# Power.net
KiCad netlist of a schematic drawn in Altium Designer
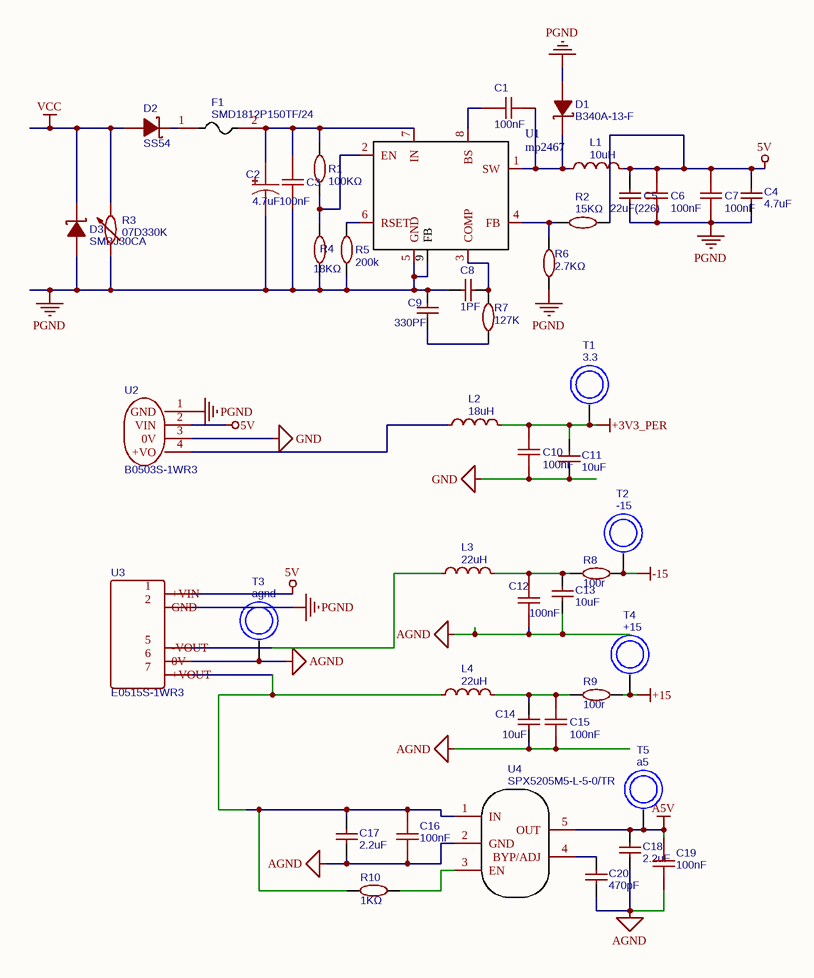
[diagram p0: Power.SchDoc]

(export (version "E")
  (design (tool "Eeschema 10.0.6"))
  (components
    (comp (ref "C1")
      (value "100nF")
      (footprint "0603 - cap")
      (fields (field (name "BOM_MANUFACTURER PART") "CC0603KRX7R9BB104"))
      (libsource (lib "") (part "root_2___1"))
    )
    (comp (ref "C2")
      (value "4.7uF")
      (footprint "CAP-6.3*5.4")
      (fields (field (name "BOM_MANUFACTURER PART") "RVT2A4R7M0605"))
      (libsource (lib "") (part "root_0___8"))
    )
    (comp (ref "C3")
      (value "100nF")
      (footprint "0603 - cap")
      (fields (field (name "BOM_MANUFACTURER PART") "CC0603KRX7R9BB104"))
      (libsource (lib "") (part "root_1___1"))
    )
    (comp (ref "C4")
      (value "4.7uF")
      (footprint "1206 - cap")
      (fields (field (name "BOM_MANUFACTURER PART") "1206B475K500NT"))
      (libsource (lib "") (part "root_1___3"))
    )
    (comp (ref "C5")
      (value "22uF(226)")
      (footprint "1206 - cap")
      (fields (field (name "BOM_MANUFACTURER PART") "1206F226M100NT") (field (name "CONTRIBUTOR") "LCSC"))
      (libsource (lib "altium-import") (part "root_1__"))
    )
    (comp (ref "C6")
      (value "100nF")
      (footprint "0603 - cap")
      (fields (field (name "BOM_MANUFACTURER PART") "CC0603KRX7R9BB104"))
      (libsource (lib "") (part "root_1___1"))
    )
    (comp (ref "C7")
      (value "100nF")
      (footprint "0603 - cap")
      (fields (field (name "BOM_MANUFACTURER PART") "CC0603KRX7R9BB104"))
      (libsource (lib "") (part "root_1___1"))
    )
    (comp (ref "C8")
      (value "1PF")
      (footprint "0603 - cap")
      (fields (field (name "BOM_MANUFACTURER PART") "0603B472K500NT"))
      (libsource (lib "altium-import") (part "root_2__"))
    )
    (comp (ref "C9")
      (value "330PF")
      (footprint "0603 - cap")
      (fields (field (name "BOM_MANUFACTURER PART") "0603B472K500NT"))
      (libsource (lib "") (part "root_1___3"))
    )
    (comp (ref "C10")
      (value "100nF")
      (footprint "0603 - cap")
      (fields (field (name "BOM_MANUFACTURER PART") "CC0603KRX7R9BB104"))
      (libsource (lib "") (part "root_1___1"))
    )
    (comp (ref "C11")
      (value "10uF")
      (footprint "1206 - cap")
      (fields (field (name "BOM_MANUFACTURER PART") "CL31B225KBHNNNE"))
      (libsource (lib "altium-import") (part "root_3__"))
    )
    (comp (ref "C12")
      (value "100nF")
      (footprint "0603 - cap")
      (fields (field (name "BOM_MANUFACTURER PART") "CC0603KRX7R9BB104"))
      (libsource (lib "") (part "root_1___1"))
    )
    (comp (ref "C13")
      (value "10uF")
      (footprint "1206 - cap")
      (fields (field (name "BOM_MANUFACTURER PART") "CL31B225KBHNNNE"))
      (libsource (lib "altium-import") (part "root_3__"))
    )
    (comp (ref "C14")
      (value "10uF")
      (footprint "1206 - cap")
      (fields (field (name "BOM_MANUFACTURER PART") "CL31B225KBHNNNE"))
      (libsource (lib "altium-import") (part "root_3__"))
    )
    (comp (ref "C15")
      (value "100nF")
      (footprint "0603 - cap")
      (fields (field (name "BOM_MANUFACTURER PART") "CC0603KRX7R9BB104"))
      (libsource (lib "") (part "root_1___1"))
    )
    (comp (ref "C16")
      (value "100nF")
      (footprint "0603 - cap")
      (fields (field (name "BOM_MANUFACTURER PART") "CC0603KRX7R9BB104"))
      (libsource (lib "") (part "root_3___1"))
    )
    (comp (ref "C17")
      (value "2.2uF")
      (footprint "1206 - cap")
      (fields (field (name "BOM_MANUFACTURER PART") "CL31B225KBHNNNE"))
      (libsource (lib "altium-import") (part "root_3__"))
    )
    (comp (ref "C18")
      (value "2.2uF")
      (footprint "1206 - cap")
      (fields (field (name "BOM_MANUFACTURER PART") "CL31B225KBHNNNE"))
      (libsource (lib "") (part "root_1___4"))
    )
    (comp (ref "C19")
      (value "100nF")
      (footprint "0603 - cap")
      (fields (field (name "BOM_MANUFACTURER PART") "CC0603KRX7R9BB104"))
      (libsource (lib "") (part "root_1___1"))
    )
    (comp (ref "C20")
      (value "470pF")
      (footprint "0603 - cap")
      (fields (field (name "BOM_MANUFACTURER PART") "0603B471K500NT"))
      (libsource (lib "") (part "root_1___3"))
    )
    (comp (ref "D1")
      (value "B340A-13-F")
      (footprint "SMA(DO-214AC)")
      (libsource (lib "") (part "root_1___5"))
    )
    (comp (ref "D2") (value "SS54") (footprint "SMA(DO-214AC)") (libsource (lib "") (part "root_0___4")))
    (comp (ref "D3") (value "SMBJ30CA") (footprint "SMB(DO-214AA)") (libsource (lib "") (part "root_0___6")))
    (comp (ref "F1") (value "SMD1812P150TF/24") (footprint "1812") (libsource (lib "") (part "root_0___5")))
    (comp (ref "L1")
      (value "10uH")
      (footprint "8040")
      (fields (field (name "BOM_MANUFACTURER PART") "VLP8040T-100M"))
      (libsource (lib "altium-import") (part "root_0__"))
    )
    (comp (ref "L2")
      (value "18uH")
      (footprint "1220")
      (fields (field (name "BOM_MANUFACTURER PART") "SPH252012H180MT"))
      (libsource (lib "") (part "root_0___3"))
    )
    (comp (ref "L3")
      (value "22uH")
      (footprint "IND_0805")
      (fields (field (name "BOM_MANUFACTURER PART") "VLP8040T-100M"))
      (libsource (lib "altium-import") (part "root_0__"))
    )
    (comp (ref "L4")
      (value "22uH")
      (footprint "IND_0805")
      (fields (field (name "BOM_MANUFACTURER PART") "VLP8040T-100M"))
      (libsource (lib "altium-import") (part "root_0__"))
    )
    (comp (ref "R1")
      (value "100KΩ")
      (footprint "0603-res")
      (fields (field (name "BOM_MANUFACTURER PART") "0603WAF1003T5E"))
      (libsource (lib "") (part "root_1___2"))
    )
    (comp (ref "R2")
      (value "15KΩ")
      (footprint "0603-res")
      (fields (field (name "BOM_MANUFACTURER PART") "0603WAF2002T5E"))
      (libsource (lib "") (part "root_0___2"))
    )
    (comp (ref "R3") (value "07D330K") (footprint "PS-RES-9*4.7") (libsource (lib "") (part "root_1___6")))
    (comp (ref "R4")
      (value "18KΩ")
      (footprint "0603-res")
      (fields (field (name "BOM_MANUFACTURER PART") "0603WAF1502T5E"))
      (libsource (lib "") (part "root_1___2"))
    )
    (comp (ref "R5")
      (value "200k")
      (footprint "0603-res")
      (fields (field (name "BOM_MANUFACTURER PART") "0603WAF1502T5E"))
      (libsource (lib "") (part "root_1___2"))
    )
    (comp (ref "R6")
      (value "2.7KΩ")
      (footprint "0603-res")
      (fields (field (name "BOM_MANUFACTURER PART") "0603WAF2002T5E"))
      (libsource (lib "") (part "root_1___2"))
    )
    (comp (ref "R7")
      (value "127K")
      (footprint "0603-res")
      (fields (field (name "BOM_MANUFACTURER PART") "0603WAF1302T5E"))
      (libsource (lib "") (part "root_1___2"))
    )
    (comp (ref "R8")
      (value "100r")
      (footprint "1206-res")
      (fields (field (name "BOM_MANUFACTURER PART") "0603WAF1001T5E"))
      (libsource (lib "") (part "root_0___2"))
    )
    (comp (ref "R9")
      (value "100r")
      (footprint "1206-res")
      (fields (field (name "BOM_MANUFACTURER PART") "0603WAF1001T5E"))
      (libsource (lib "") (part "root_0___2"))
    )
    (comp (ref "R10")
      (value "1KΩ")
      (footprint "0603-res")
      (fields (field (name "BOM_MANUFACTURER PART") "0603WAF2002T5E"))
      (libsource (lib "") (part "root_0___2"))
    )
    (comp (ref "T1")
      (value "3.3")
      (footprint "tp")
      (fields (field (name "BOM_MANUFACTURER PART") "?"))
      (libsource (lib "") (part "root_0___1"))
    )
    (comp (ref "T2")
      (value "-15")
      (footprint "tp")
      (fields (field (name "BOM_MANUFACTURER PART") "?"))
      (libsource (lib "") (part "root_0___1"))
    )
    (comp (ref "T3")
      (value "agnd")
      (footprint "tp")
      (fields (field (name "BOM_MANUFACTURER PART") "?"))
      (libsource (lib "") (part "root_0___1"))
    )
    (comp (ref "T4")
      (value "+15")
      (footprint "tp")
      (fields (field (name "BOM_MANUFACTURER PART") "?"))
      (libsource (lib "") (part "root_0___1"))
    )
    (comp (ref "T5")
      (value "a5")
      (footprint "tp")
      (fields (field (name "BOM_MANUFACTURER PART") "?"))
      (libsource (lib "") (part "root_0___1"))
    )
    (comp (ref "U1") (value "mp2467") (footprint "ESOP-8-EP") (libsource (lib "TcpControl") (part "mp2467")))
    (comp (ref "U2")
      (value "B0503S-1WR3")
      (footprint "B0505S-1WR2")
      (libsource (lib "altium-import") (part "root_3_mirrored__"))
    )
    (comp (ref "U3")
      (value "E0515S-1WR3")
      (footprint "E0515S-1WR3")
      (libsource (lib "altium-import") (part "root_0_mirrored__"))
    )
    (comp (ref "U4")
      (value "SPX5205M5-L-5-0/TR")
      (footprint "SOT-23-5")
      (libsource (lib "") (part "root_0___7"))
    )
  )
  (nets
    (net (code "1") (name "+3V3_PER") (class "Default")
      (node (ref "C10") (pin "2") (pinfunction "2_2") (pintype "passive"))
      (node (ref "C11") (pin "1") (pinfunction "1_1") (pintype "passive"))
      (node (ref "L2") (pin "2") (pinfunction "2_2") (pintype "passive"))
      (node (ref "T1") (pin "1") (pintype "passive"))
    )
    (net (code "2") (name "+15") (class "Default")
      (node (ref "R9") (pin "2") (pinfunction "2_2") (pintype "passive"))
      (node (ref "T4") (pin "1") (pintype "passive"))
    )
    (net (code "3") (name "-15") (class "Default")
      (node (ref "R8") (pin "2") (pinfunction "2_2") (pintype "passive"))
      (node (ref "T2") (pin "1") (pintype "passive"))
    )
    (net (code "4") (name "5V") (class "Default")
      (node (ref "C4") (pin "2") (pinfunction "2_2") (pintype "passive"))
      (node (ref "C5") (pin "2") (pinfunction "2_2") (pintype "passive"))
      (node (ref "C6") (pin "2") (pinfunction "2_2") (pintype "passive"))
      (node (ref "C7") (pin "2") (pinfunction "2_2") (pintype "passive"))
      (node (ref "L1") (pin "2") (pinfunction "2_2") (pintype "passive"))
      (node (ref "R2") (pin "2") (pinfunction "2_2") (pintype "passive"))
      (node (ref "U2") (pin "2") (pinfunction "VIN_2") (pintype "passive"))
      (node (ref "U3") (pin "1") (pinfunction "+VIN_1") (pintype "passive"))
    )
    (net (code "5") (name "A5V") (class "Default")
      (node (ref "C18") (pin "2") (pinfunction "2_2") (pintype "passive"))
      (node (ref "C19") (pin "2") (pinfunction "2_2") (pintype "passive"))
      (node (ref "T5") (pin "1") (pintype "passive"))
      (node (ref "U4") (pin "5") (pinfunction "OUT_5") (pintype "passive"))
    )
    (net (code "6") (name "AGND") (class "Default")
      (node (ref "C12") (pin "1") (pinfunction "1_1") (pintype "passive"))
      (node (ref "C13") (pin "2") (pinfunction "2_2") (pintype "passive"))
      (node (ref "C14") (pin "2") (pinfunction "2_2") (pintype "passive"))
      (node (ref "C15") (pin "1") (pinfunction "1_1") (pintype "passive"))
      (node (ref "C16") (pin "2") (pinfunction "2_2") (pintype "passive"))
      (node (ref "C17") (pin "2") (pinfunction "2_2") (pintype "passive"))
      (node (ref "C18") (pin "1") (pinfunction "1_1") (pintype "passive"))
      (node (ref "C19") (pin "1") (pinfunction "1_1") (pintype "passive"))
      (node (ref "C20") (pin "1") (pinfunction "1_1") (pintype "passive"))
      (node (ref "T3") (pin "1") (pintype "passive"))
      (node (ref "U3") (pin "6") (pinfunction "0V_6") (pintype "passive"))
      (node (ref "U4") (pin "2") (pinfunction "GND_2") (pintype "passive"))
    )
    (net (code "7") (name "GND") (class "Default")
      (node (ref "C10") (pin "1") (pinfunction "1_1") (pintype "passive"))
      (node (ref "C11") (pin "2") (pinfunction "2_2") (pintype "passive"))
      (node (ref "U2") (pin "3") (pinfunction "0V_3") (pintype "passive"))
    )
    (net (code "8") (name "Net-(C9-Pad1)") (class "Default")
      (node (ref "C9") (pin "1") (pinfunction "1_1") (pintype "passive"))
      (node (ref "R7") (pin "1") (pinfunction "1_1") (pintype "passive"))
    )
    (net (code "9") (name "Net-(C12-Pad2)") (class "Default")
      (node (ref "C12") (pin "2") (pinfunction "2_2") (pintype "passive"))
      (node (ref "C13") (pin "1") (pinfunction "1_1") (pintype "passive"))
      (node (ref "L3") (pin "2") (pinfunction "2_2") (pintype "passive"))
      (node (ref "R8") (pin "1") (pinfunction "1_1") (pintype "passive"))
    )
    (net (code "10") (name "Net-(C14-Pad1)") (class "Default")
      (node (ref "C14") (pin "1") (pinfunction "1_1") (pintype "passive"))
      (node (ref "C15") (pin "2") (pinfunction "2_2") (pintype "passive"))
      (node (ref "L4") (pin "2") (pinfunction "2_2") (pintype "passive"))
      (node (ref "R9") (pin "1") (pinfunction "1_1") (pintype "passive"))
    )
    (net (code "11") (name "Net-(D1-K)") (class "Default")
      (node (ref "C1") (pin "1") (pinfunction "1_1") (pintype "passive"))
      (node (ref "D1") (pin "2") (pinfunction "K_2") (pintype "passive"))
      (node (ref "L1") (pin "1") (pinfunction "1_1") (pintype "passive"))
      (node (ref "U1") (pin "1") (pinfunction "SW_1") (pintype "passive"))
    )
    (net (code "12") (name "Net-(D2-K)") (class "Default")
      (node (ref "D2") (pin "2") (pinfunction "K_2") (pintype "passive"))
      (node (ref "F1") (pin "1") (pinfunction "1_1") (pintype "passive"))
    )
    (net (code "13") (name "Net-(R2-Pad1)") (class "Default")
      (node (ref "R2") (pin "1") (pinfunction "1_1") (pintype "passive"))
      (node (ref "R6") (pin "2") (pinfunction "2_2") (pintype "passive"))
      (node (ref "U1") (pin "4") (pinfunction "FB_4") (pintype "passive"))
    )
    (net (code "14") (name "Net-(U1-BS)") (class "Default")
      (node (ref "C1") (pin "2") (pinfunction "2_2") (pintype "passive"))
      (node (ref "U1") (pin "8") (pinfunction "BS_8") (pintype "passive"))
    )
    (net (code "15") (name "Net-(U1-COMP)") (class "Default")
      (node (ref "C8") (pin "1") (pinfunction "1_1") (pintype "passive"))
      (node (ref "R7") (pin "2") (pinfunction "2_2") (pintype "passive"))
      (node (ref "U1") (pin "3") (pinfunction "COMP_3") (pintype "passive"))
    )
    (net (code "16") (name "Net-(U1-EN)") (class "Default")
      (node (ref "R1") (pin "1") (pinfunction "1_1") (pintype "passive"))
      (node (ref "R4") (pin "2") (pinfunction "2_2") (pintype "passive"))
      (node (ref "U1") (pin "2") (pinfunction "EN_2") (pintype "passive"))
    )
    (net (code "17") (name "Net-(U1-IN)") (class "Default")
      (node (ref "C2") (pin "1") (pinfunction "1_1") (pintype "passive"))
      (node (ref "C3") (pin "2") (pinfunction "2_2") (pintype "passive"))
      (node (ref "F1") (pin "2") (pinfunction "2_2") (pintype "passive"))
      (node (ref "R1") (pin "2") (pinfunction "2_2") (pintype "passive"))
      (node (ref "U1") (pin "7") (pinfunction "IN_7") (pintype "passive"))
    )
    (net (code "18") (name "Net-(U1-RSET)") (class "Default")
      (node (ref "R5") (pin "2") (pinfunction "2_2") (pintype "passive"))
      (node (ref "U1") (pin "6") (pinfunction "RSET_6") (pintype "passive"))
    )
    (net (code "19") (name "Net-(U2-+VO)") (class "Default")
      (node (ref "L2") (pin "1") (pinfunction "1_1") (pintype "passive"))
      (node (ref "U2") (pin "4") (pinfunction "+VO_4") (pintype "passive"))
    )
    (net (code "20") (name "Net-(U3-+VOUT)") (class "Default")
      (node (ref "C16") (pin "1") (pinfunction "1_1") (pintype "passive"))
      (node (ref "C17") (pin "1") (pinfunction "1_1") (pintype "passive"))
      (node (ref "L4") (pin "1") (pinfunction "1_1") (pintype "passive"))
      (node (ref "R10") (pin "1") (pinfunction "1_1") (pintype "passive"))
      (node (ref "U3") (pin "7") (pinfunction "+VOUT_7") (pintype "passive"))
      (node (ref "U4") (pin "1") (pinfunction "IN_1") (pintype "passive"))
    )
    (net (code "21") (name "Net-(U3--VOUT)") (class "Default")
      (node (ref "L3") (pin "1") (pinfunction "1_1") (pintype "passive"))
      (node (ref "U3") (pin "5") (pinfunction "-VOUT_5") (pintype "passive"))
    )
    (net (code "22") (name "Net-(U4-BYP{slash}ADJ)") (class "Default")
      (node (ref "C20") (pin "2") (pinfunction "2_2") (pintype "passive"))
      (node (ref "U4") (pin "4") (pinfunction "BYP/ADJ_4") (pintype "passive"))
    )
    (net (code "23") (name "Net-(U4-EN)") (class "Default")
      (node (ref "R10") (pin "2") (pinfunction "2_2") (pintype "passive"))
      (node (ref "U4") (pin "3") (pinfunction "EN_3") (pintype "passive"))
    )
    (net (code "24") (name "PGND") (class "Default")
      (node (ref "C2") (pin "2") (pinfunction "2_2") (pintype "passive"))
      (node (ref "C3") (pin "1") (pinfunction "1_1") (pintype "passive"))
      (node (ref "C4") (pin "1") (pinfunction "1_1") (pintype "passive"))
      (node (ref "C5") (pin "1") (pinfunction "1_1") (pintype "passive"))
      (node (ref "C6") (pin "1") (pinfunction "1_1") (pintype "passive"))
      (node (ref "C7") (pin "1") (pinfunction "1_1") (pintype "passive"))
      (node (ref "C8") (pin "2") (pinfunction "2_2") (pintype "passive"))
      (node (ref "C9") (pin "2") (pinfunction "2_2") (pintype "passive"))
      (node (ref "D1") (pin "1") (pinfunction "A_1") (pintype "passive"))
      (node (ref "D3") (pin "1") (pinfunction "A_1") (pintype "passive"))
      (node (ref "R3") (pin "1") (pinfunction "1_1") (pintype "passive"))
      (node (ref "R4") (pin "1") (pinfunction "1_1") (pintype "passive"))
      (node (ref "R5") (pin "1") (pinfunction "1_1") (pintype "passive"))
      (node (ref "R6") (pin "1") (pinfunction "1_1") (pintype "passive"))
      (node (ref "U1") (pin "5") (pinfunction "GND_5") (pintype "passive"))
      (node (ref "U1") (pin "9") (pinfunction "FB_9") (pintype "passive"))
      (node (ref "U2") (pin "1") (pinfunction "GND_1") (pintype "passive"))
      (node (ref "U3") (pin "2") (pinfunction "GND_2") (pintype "passive"))
    )
    (net (code "25") (name "VCC") (class "Default")
      (node (ref "D2") (pin "1") (pinfunction "A_1") (pintype "passive"))
      (node (ref "D3") (pin "2") (pinfunction "K_2") (pintype "passive"))
      (node (ref "R3") (pin "2") (pinfunction "2_2") (pintype "passive"))
    )
  )
)
